# anemometer.net
KiCad netlist of a schematic drawn in EAGLE
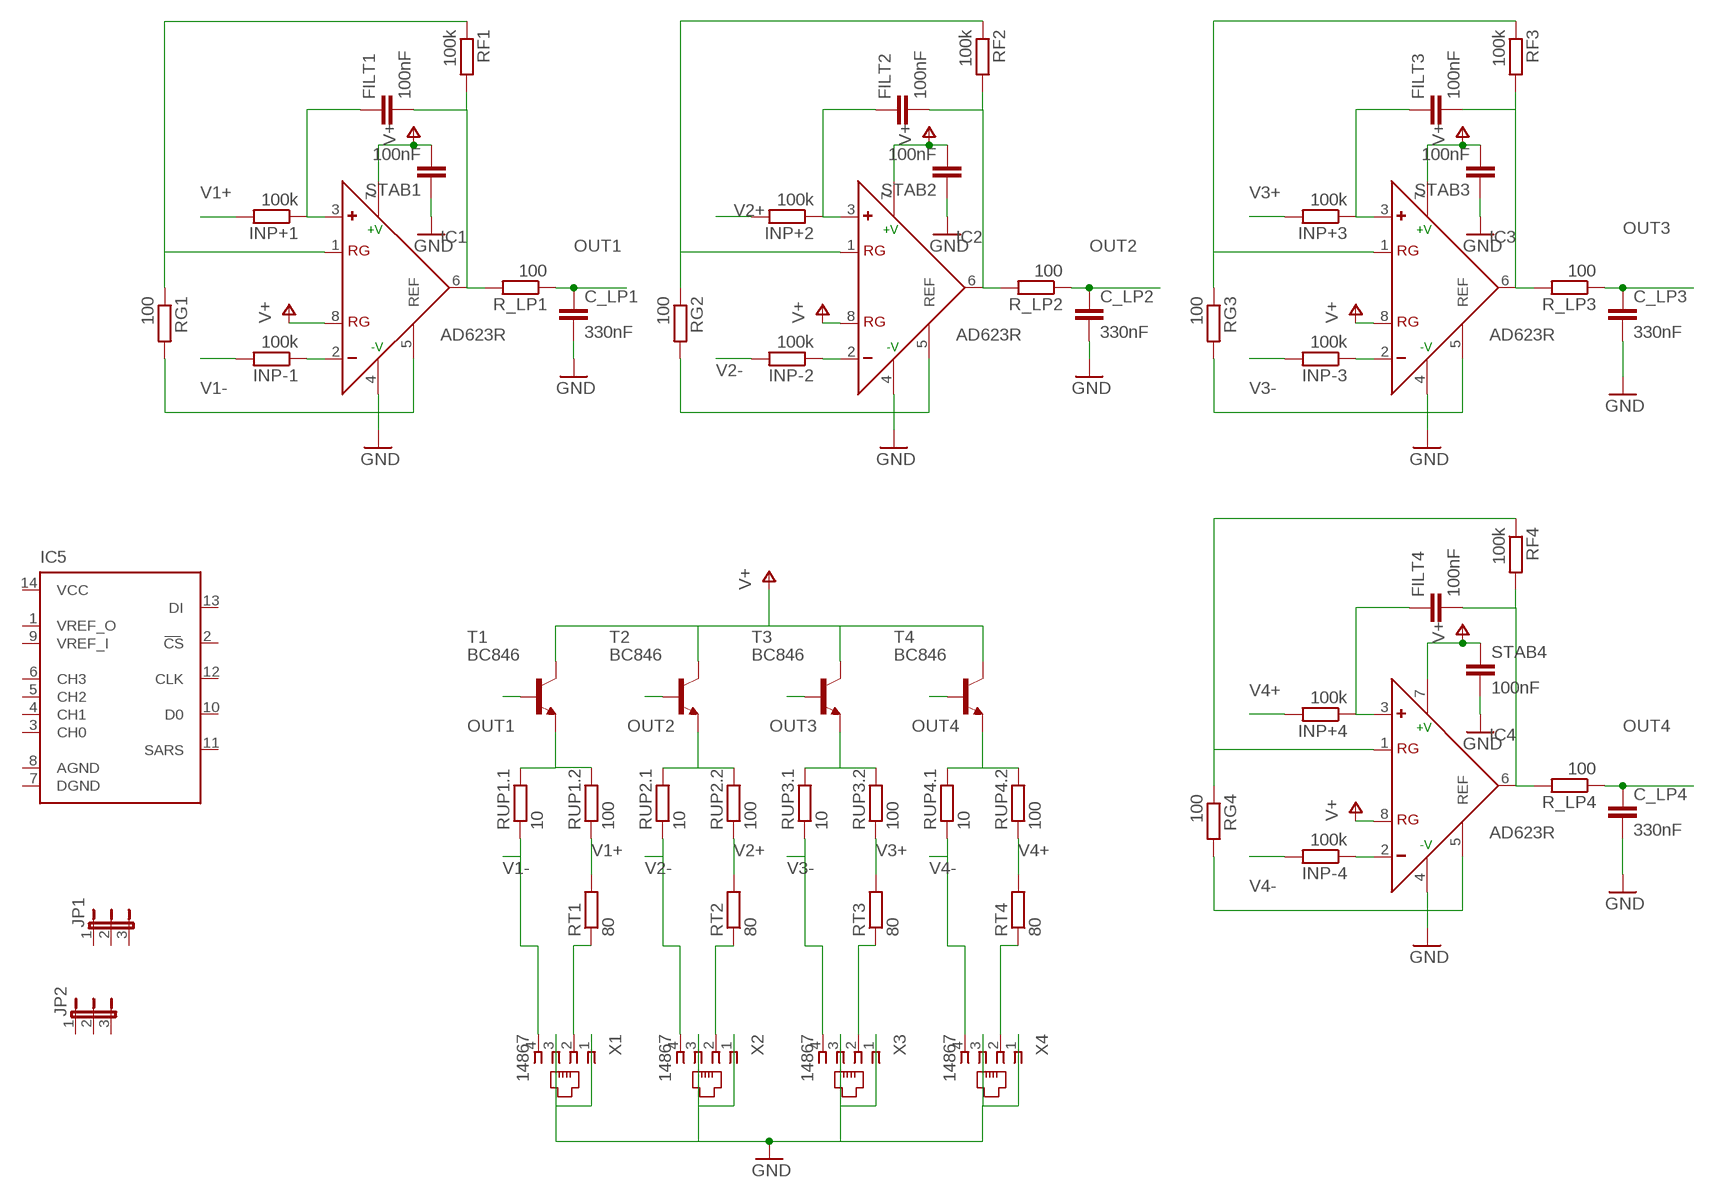
[diagram p0: schematic, sheet 1]

(export (version "E")
  (design (tool "Eeschema 10.0.6"))
  (components
    (comp (ref "C_LP1")
      (value "330nF")
      (footprint "eagle-import:C1206")
      (libsource (lib "eagle-import") (part "C-EUC1206"))
    )
    (comp (ref "C_LP2")
      (value "330nF")
      (footprint "eagle-import:C1206")
      (libsource (lib "eagle-import") (part "C-EUC1206"))
    )
    (comp (ref "C_LP3")
      (value "330nF")
      (footprint "eagle-import:C1206")
      (libsource (lib "eagle-import") (part "C-EUC1206"))
    )
    (comp (ref "C_LP4")
      (value "330nF")
      (footprint "eagle-import:C1206")
      (libsource (lib "eagle-import") (part "C-EUC1206"))
    )
    (comp (ref "FILT1")
      (value "100nF")
      (footprint "eagle-import:C1206")
      (libsource (lib "eagle-import") (part "C-EUC1206"))
    )
    (comp (ref "FILT2")
      (value "100nF")
      (footprint "eagle-import:C1206")
      (libsource (lib "eagle-import") (part "C-EUC1206"))
    )
    (comp (ref "FILT3")
      (value "100nF")
      (footprint "eagle-import:C1206")
      (libsource (lib "eagle-import") (part "C-EUC1206"))
    )
    (comp (ref "FILT4")
      (value "100nF")
      (footprint "eagle-import:C1206")
      (libsource (lib "eagle-import") (part "C-EUC1206"))
    )
    (comp (ref "IC1")
      (value "AD623R")
      (footprint "eagle-import:SO8")
      (fields (field (name "MPN") "AD623ARZ."))
      (libsource (lib "eagle-import") (part "AD623R"))
    )
    (comp (ref "IC2")
      (value "AD623R")
      (footprint "eagle-import:SO8")
      (fields (field (name "MPN") "AD623ARZ."))
      (libsource (lib "eagle-import") (part "AD623R"))
    )
    (comp (ref "IC3")
      (value "AD623R")
      (footprint "eagle-import:SO8")
      (fields (field (name "MPN") "AD623ARZ."))
      (libsource (lib "eagle-import") (part "AD623R"))
    )
    (comp (ref "IC4")
      (value "AD623R")
      (footprint "eagle-import:SO8")
      (fields (field (name "MPN") "AD623ARZ."))
      (libsource (lib "eagle-import") (part "AD623R"))
    )
    (comp (ref "IC5")
      (value "ADC08034D")
      (footprint "eagle-import:SO14")
      (libsource (lib "eagle-import") (part "ADC08034D"))
    )
    (comp (ref "INP+1")
      (value "100k")
      (footprint "eagle-import:M1206")
      (libsource (lib "eagle-import") (part "R-EU_M1206"))
    )
    (comp (ref "INP+2")
      (value "100k")
      (footprint "eagle-import:M1206")
      (libsource (lib "eagle-import") (part "R-EU_M1206"))
    )
    (comp (ref "INP+3")
      (value "100k")
      (footprint "eagle-import:M1206")
      (libsource (lib "eagle-import") (part "R-EU_M1206"))
    )
    (comp (ref "INP+4")
      (value "100k")
      (footprint "eagle-import:M1206")
      (libsource (lib "eagle-import") (part "R-EU_M1206"))
    )
    (comp (ref "INP-1")
      (value "100k")
      (footprint "eagle-import:M1206")
      (libsource (lib "eagle-import") (part "R-EU_M1206"))
    )
    (comp (ref "INP-2")
      (value "100k")
      (footprint "eagle-import:M1206")
      (libsource (lib "eagle-import") (part "R-EU_M1206"))
    )
    (comp (ref "INP-3")
      (value "100k")
      (footprint "eagle-import:M1206")
      (libsource (lib "eagle-import") (part "R-EU_M1206"))
    )
    (comp (ref "INP-4")
      (value "100k")
      (footprint "eagle-import:M1206")
      (libsource (lib "eagle-import") (part "R-EU_M1206"))
    )
    (comp (ref "JP1")
      (value "JP2E")
      (footprint "eagle-import:JP2")
      (libsource (lib "eagle-import") (part "JP2E"))
    )
    (comp (ref "JP2")
      (value "JP2E")
      (footprint "eagle-import:JP2")
      (libsource (lib "eagle-import") (part "JP2E"))
    )
    (comp (ref "RF1")
      (value "100k")
      (footprint "eagle-import:M1206")
      (libsource (lib "eagle-import") (part "R-EU_M1206"))
    )
    (comp (ref "RF2")
      (value "100k")
      (footprint "eagle-import:M1206")
      (libsource (lib "eagle-import") (part "R-EU_M1206"))
    )
    (comp (ref "RF3")
      (value "100k")
      (footprint "eagle-import:M1206")
      (libsource (lib "eagle-import") (part "R-EU_M1206"))
    )
    (comp (ref "RF4")
      (value "100k")
      (footprint "eagle-import:M1206")
      (libsource (lib "eagle-import") (part "R-EU_M1206"))
    )
    (comp (ref "RG1")
      (value "100")
      (footprint "eagle-import:M1206")
      (libsource (lib "eagle-import") (part "R-EU_M1206"))
    )
    (comp (ref "RG2")
      (value "100")
      (footprint "eagle-import:M1206")
      (libsource (lib "eagle-import") (part "R-EU_M1206"))
    )
    (comp (ref "RG3")
      (value "100")
      (footprint "eagle-import:M1206")
      (libsource (lib "eagle-import") (part "R-EU_M1206"))
    )
    (comp (ref "RG4")
      (value "100")
      (footprint "eagle-import:M1206")
      (libsource (lib "eagle-import") (part "R-EU_M1206"))
    )
    (comp (ref "RT1")
      (value "80")
      (footprint "eagle-import:R1206")
      (libsource (lib "eagle-import") (part "R-EU_R1206"))
    )
    (comp (ref "RT2")
      (value "80")
      (footprint "eagle-import:R1206")
      (libsource (lib "eagle-import") (part "R-EU_R1206"))
    )
    (comp (ref "RT3")
      (value "80")
      (footprint "eagle-import:R1206")
      (libsource (lib "eagle-import") (part "R-EU_R1206"))
    )
    (comp (ref "RT4")
      (value "80")
      (footprint "eagle-import:R1206")
      (libsource (lib "eagle-import") (part "R-EU_R1206"))
    )
    (comp (ref "RUP1.1")
      (value "10")
      (footprint "eagle-import:R1206")
      (libsource (lib "eagle-import") (part "R-EU_R1206"))
    )
    (comp (ref "RUP1.2")
      (value "100")
      (footprint "eagle-import:R1206")
      (libsource (lib "eagle-import") (part "R-EU_R1206"))
    )
    (comp (ref "RUP2.1")
      (value "10")
      (footprint "eagle-import:R1206")
      (libsource (lib "eagle-import") (part "R-EU_R1206"))
    )
    (comp (ref "RUP2.2")
      (value "100")
      (footprint "eagle-import:R1206")
      (libsource (lib "eagle-import") (part "R-EU_R1206"))
    )
    (comp (ref "RUP3.1")
      (value "10")
      (footprint "eagle-import:R1206")
      (libsource (lib "eagle-import") (part "R-EU_R1206"))
    )
    (comp (ref "RUP3.2")
      (value "100")
      (footprint "eagle-import:R1206")
      (libsource (lib "eagle-import") (part "R-EU_R1206"))
    )
    (comp (ref "RUP4.1")
      (value "10")
      (footprint "eagle-import:R1206")
      (libsource (lib "eagle-import") (part "R-EU_R1206"))
    )
    (comp (ref "RUP4.2")
      (value "100")
      (footprint "eagle-import:R1206")
      (libsource (lib "eagle-import") (part "R-EU_R1206"))
    )
    (comp (ref "R_LP1")
      (value "100")
      (footprint "eagle-import:M1206")
      (libsource (lib "eagle-import") (part "R-EU_M1206"))
    )
    (comp (ref "R_LP2")
      (value "100")
      (footprint "eagle-import:M1206")
      (libsource (lib "eagle-import") (part "R-EU_M1206"))
    )
    (comp (ref "R_LP3")
      (value "100")
      (footprint "eagle-import:M1206")
      (libsource (lib "eagle-import") (part "R-EU_M1206"))
    )
    (comp (ref "R_LP4")
      (value "100")
      (footprint "eagle-import:M1206")
      (libsource (lib "eagle-import") (part "R-EU_M1206"))
    )
    (comp (ref "STAB1")
      (value "100nF")
      (footprint "eagle-import:C1206")
      (libsource (lib "eagle-import") (part "C-EUC1206"))
    )
    (comp (ref "STAB2")
      (value "100nF")
      (footprint "eagle-import:C1206")
      (libsource (lib "eagle-import") (part "C-EUC1206"))
    )
    (comp (ref "STAB3")
      (value "100nF")
      (footprint "eagle-import:C1206")
      (libsource (lib "eagle-import") (part "C-EUC1206"))
    )
    (comp (ref "STAB4")
      (value "100nF")
      (footprint "eagle-import:C1206")
      (libsource (lib "eagle-import") (part "C-EUC1206"))
    )
    (comp (ref "T1")
      (value "BC846")
      (footprint "eagle-import:SOT23")
      (libsource (lib "eagle-import") (part "BC846"))
    )
    (comp (ref "T2")
      (value "BC846")
      (footprint "eagle-import:SOT23")
      (libsource (lib "eagle-import") (part "BC846"))
    )
    (comp (ref "T3")
      (value "BC846")
      (footprint "eagle-import:SOT23")
      (libsource (lib "eagle-import") (part "BC846"))
    )
    (comp (ref "T4")
      (value "BC846")
      (footprint "eagle-import:SOT23")
      (libsource (lib "eagle-import") (part "BC846"))
    )
    (comp (ref "X1")
      (value "14867")
      (footprint "eagle-import:14867")
      (libsource (lib "eagle-import") (part "14867"))
    )
    (comp (ref "X2")
      (value "14867")
      (footprint "eagle-import:14867")
      (libsource (lib "eagle-import") (part "14867"))
    )
    (comp (ref "X3")
      (value "14867")
      (footprint "eagle-import:14867")
      (libsource (lib "eagle-import") (part "14867"))
    )
    (comp (ref "X4")
      (value "14867")
      (footprint "eagle-import:14867")
      (libsource (lib "eagle-import") (part "14867"))
    )
  )
  (nets
    (net (code "1") (name "/AGND") (class "Default")
      (node (ref "IC5") (pin "8") (pinfunction "AGND_8") (pintype "power_in"))
    )
    (net (code "2") (name "/DGND") (class "Default")
      (node (ref "IC5") (pin "7") (pinfunction "DGND_7") (pintype "power_in"))
    )
    (net (code "3") (name "/OUT1") (class "Default")
      (node (ref "C_LP1") (pin "1") (pinfunction "1_1") (pintype "passive"))
      (node (ref "R_LP1") (pin "1") (pinfunction "1_1") (pintype "passive"))
      (node (ref "T1") (pin "1") (pinfunction "B_1") (pintype "passive"))
    )
    (net (code "4") (name "/OUT2") (class "Default")
      (node (ref "C_LP2") (pin "1") (pinfunction "1_1") (pintype "passive"))
      (node (ref "R_LP2") (pin "1") (pinfunction "1_1") (pintype "passive"))
      (node (ref "T2") (pin "1") (pinfunction "B_1") (pintype "passive"))
    )
    (net (code "5") (name "/OUT3") (class "Default")
      (node (ref "C_LP3") (pin "1") (pinfunction "1_1") (pintype "passive"))
      (node (ref "R_LP3") (pin "1") (pinfunction "1_1") (pintype "passive"))
      (node (ref "T3") (pin "1") (pinfunction "B_1") (pintype "passive"))
    )
    (net (code "6") (name "/OUT4") (class "Default")
      (node (ref "C_LP4") (pin "1") (pinfunction "1_1") (pintype "passive"))
      (node (ref "R_LP4") (pin "1") (pinfunction "1_1") (pintype "passive"))
      (node (ref "T4") (pin "1") (pinfunction "B_1") (pintype "passive"))
    )
    (net (code "7") (name "/V1+") (class "Default")
      (node (ref "INP+1") (pin "2") (pinfunction "2_2") (pintype "passive"))
      (node (ref "RT1") (pin "2") (pinfunction "2_2") (pintype "passive"))
      (node (ref "RUP1.2") (pin "1") (pinfunction "1_1") (pintype "passive"))
    )
    (net (code "8") (name "/V1-") (class "Default")
      (node (ref "INP-1") (pin "2") (pinfunction "2_2") (pintype "passive"))
      (node (ref "RUP1.1") (pin "1") (pinfunction "1_1") (pintype "passive"))
      (node (ref "X1") (pin "4") (pinfunction "4_4") (pintype "passive"))
    )
    (net (code "9") (name "/V2+") (class "Default")
      (node (ref "INP+2") (pin "2") (pinfunction "2_2") (pintype "passive"))
      (node (ref "RT2") (pin "2") (pinfunction "2_2") (pintype "passive"))
      (node (ref "RUP2.2") (pin "1") (pinfunction "1_1") (pintype "passive"))
    )
    (net (code "10") (name "/V2-") (class "Default")
      (node (ref "INP-2") (pin "2") (pinfunction "2_2") (pintype "passive"))
      (node (ref "RUP2.1") (pin "1") (pinfunction "1_1") (pintype "passive"))
      (node (ref "X2") (pin "4") (pinfunction "4_4") (pintype "passive"))
    )
    (net (code "11") (name "/V3+") (class "Default")
      (node (ref "INP+3") (pin "2") (pinfunction "2_2") (pintype "passive"))
      (node (ref "RT3") (pin "2") (pinfunction "2_2") (pintype "passive"))
      (node (ref "RUP3.2") (pin "1") (pinfunction "1_1") (pintype "passive"))
    )
    (net (code "12") (name "/V3-") (class "Default")
      (node (ref "INP-3") (pin "2") (pinfunction "2_2") (pintype "passive"))
      (node (ref "RUP3.1") (pin "1") (pinfunction "1_1") (pintype "passive"))
      (node (ref "X3") (pin "4") (pinfunction "4_4") (pintype "passive"))
    )
    (net (code "13") (name "/V4+") (class "Default")
      (node (ref "INP+4") (pin "2") (pinfunction "2_2") (pintype "passive"))
      (node (ref "RT4") (pin "2") (pinfunction "2_2") (pintype "passive"))
      (node (ref "RUP4.2") (pin "1") (pinfunction "1_1") (pintype "passive"))
    )
    (net (code "14") (name "/V4-") (class "Default")
      (node (ref "INP-4") (pin "2") (pinfunction "2_2") (pintype "passive"))
      (node (ref "RUP4.1") (pin "1") (pinfunction "1_1") (pintype "passive"))
      (node (ref "X4") (pin "4") (pinfunction "4_4") (pintype "passive"))
    )
    (net (code "15") (name "/VCC") (class "Default")
      (node (ref "IC5") (pin "14") (pinfunction "VCC_14") (pintype "power_in"))
    )
    (net (code "16") (name "GND") (class "Default")
      (node (ref "C_LP1") (pin "2") (pinfunction "2_2") (pintype "passive"))
      (node (ref "C_LP2") (pin "2") (pinfunction "2_2") (pintype "passive"))
      (node (ref "C_LP3") (pin "2") (pinfunction "2_2") (pintype "passive"))
      (node (ref "C_LP4") (pin "2") (pinfunction "2_2") (pintype "passive"))
      (node (ref "IC1") (pin "4") (pinfunction "-V_4") (pintype "power_in"))
      (node (ref "IC1") (pin "5") (pinfunction "REF_5") (pintype "passive"))
      (node (ref "IC2") (pin "4") (pinfunction "-V_4") (pintype "power_in"))
      (node (ref "IC2") (pin "5") (pinfunction "REF_5") (pintype "passive"))
      (node (ref "IC3") (pin "4") (pinfunction "-V_4") (pintype "power_in"))
      (node (ref "IC3") (pin "5") (pinfunction "REF_5") (pintype "passive"))
      (node (ref "IC4") (pin "4") (pinfunction "-V_4") (pintype "power_in"))
      (node (ref "IC4") (pin "5") (pinfunction "REF_5") (pintype "passive"))
      (node (ref "RG1") (pin "2") (pinfunction "2_2") (pintype "passive"))
      (node (ref "RG2") (pin "2") (pinfunction "2_2") (pintype "passive"))
      (node (ref "RG3") (pin "2") (pinfunction "2_2") (pintype "passive"))
      (node (ref "RG4") (pin "2") (pinfunction "2_2") (pintype "passive"))
      (node (ref "STAB1") (pin "1") (pinfunction "1_1") (pintype "passive"))
      (node (ref "STAB2") (pin "1") (pinfunction "1_1") (pintype "passive"))
      (node (ref "STAB3") (pin "1") (pinfunction "1_1") (pintype "passive"))
      (node (ref "STAB4") (pin "2") (pinfunction "2_2") (pintype "passive"))
      (node (ref "X1") (pin "1") (pinfunction "1_1") (pintype "passive"))
      (node (ref "X1") (pin "3") (pinfunction "3_3") (pintype "passive"))
      (node (ref "X2") (pin "1") (pinfunction "1_1") (pintype "passive"))
      (node (ref "X2") (pin "3") (pinfunction "3_3") (pintype "passive"))
      (node (ref "X3") (pin "1") (pinfunction "1_1") (pintype "passive"))
      (node (ref "X3") (pin "3") (pinfunction "3_3") (pintype "passive"))
      (node (ref "X4") (pin "1") (pinfunction "1_1") (pintype "passive"))
      (node (ref "X4") (pin "3") (pinfunction "3_3") (pintype "passive"))
    )
    (net (code "17") (name "Net-(IC1-+)") (class "Default")
      (node (ref "FILT1") (pin "1") (pinfunction "1_1") (pintype "passive"))
      (node (ref "IC1") (pin "3") (pinfunction "+_3") (pintype "input"))
      (node (ref "INP+1") (pin "1") (pinfunction "1_1") (pintype "passive"))
    )
    (net (code "18") (name "Net-(IC1--)") (class "Default")
      (node (ref "IC1") (pin "2") (pinfunction "-_2") (pintype "input"))
      (node (ref "INP-1") (pin "1") (pinfunction "1_1") (pintype "passive"))
    )
    (net (code "19") (name "Net-(IC1-OUT)") (class "Default")
      (node (ref "FILT1") (pin "2") (pinfunction "2_2") (pintype "passive"))
      (node (ref "IC1") (pin "6") (pinfunction "OUT_6") (pintype "output"))
      (node (ref "RF1") (pin "2") (pinfunction "2_2") (pintype "passive"))
      (node (ref "R_LP1") (pin "2") (pinfunction "2_2") (pintype "passive"))
    )
    (net (code "20") (name "Net-(IC1-RG-Pad1)") (class "Default")
      (node (ref "IC1") (pin "1") (pinfunction "RG_1") (pintype "passive"))
      (node (ref "RF1") (pin "1") (pinfunction "1_1") (pintype "passive"))
      (node (ref "RG1") (pin "1") (pinfunction "1_1") (pintype "passive"))
    )
    (net (code "21") (name "Net-(IC2-+)") (class "Default")
      (node (ref "FILT2") (pin "1") (pinfunction "1_1") (pintype "passive"))
      (node (ref "IC2") (pin "3") (pinfunction "+_3") (pintype "input"))
      (node (ref "INP+2") (pin "1") (pinfunction "1_1") (pintype "passive"))
    )
    (net (code "22") (name "Net-(IC2--)") (class "Default")
      (node (ref "IC2") (pin "2") (pinfunction "-_2") (pintype "input"))
      (node (ref "INP-2") (pin "1") (pinfunction "1_1") (pintype "passive"))
    )
    (net (code "23") (name "Net-(IC2-OUT)") (class "Default")
      (node (ref "FILT2") (pin "2") (pinfunction "2_2") (pintype "passive"))
      (node (ref "IC2") (pin "6") (pinfunction "OUT_6") (pintype "output"))
      (node (ref "RF2") (pin "2") (pinfunction "2_2") (pintype "passive"))
      (node (ref "R_LP2") (pin "2") (pinfunction "2_2") (pintype "passive"))
    )
    (net (code "24") (name "Net-(IC2-RG-Pad1)") (class "Default")
      (node (ref "IC2") (pin "1") (pinfunction "RG_1") (pintype "passive"))
      (node (ref "RF2") (pin "1") (pinfunction "1_1") (pintype "passive"))
      (node (ref "RG2") (pin "1") (pinfunction "1_1") (pintype "passive"))
    )
    (net (code "25") (name "Net-(IC3-+)") (class "Default")
      (node (ref "FILT3") (pin "1") (pinfunction "1_1") (pintype "passive"))
      (node (ref "IC3") (pin "3") (pinfunction "+_3") (pintype "input"))
      (node (ref "INP+3") (pin "1") (pinfunction "1_1") (pintype "passive"))
    )
    (net (code "26") (name "Net-(IC3--)") (class "Default")
      (node (ref "IC3") (pin "2") (pinfunction "-_2") (pintype "input"))
      (node (ref "INP-3") (pin "1") (pinfunction "1_1") (pintype "passive"))
    )
    (net (code "27") (name "Net-(IC3-OUT)") (class "Default")
      (node (ref "FILT3") (pin "2") (pinfunction "2_2") (pintype "passive"))
      (node (ref "IC3") (pin "6") (pinfunction "OUT_6") (pintype "output"))
      (node (ref "RF3") (pin "2") (pinfunction "2_2") (pintype "passive"))
      (node (ref "R_LP3") (pin "2") (pinfunction "2_2") (pintype "passive"))
    )
    (net (code "28") (name "Net-(IC3-RG-Pad1)") (class "Default")
      (node (ref "IC3") (pin "1") (pinfunction "RG_1") (pintype "passive"))
      (node (ref "RF3") (pin "1") (pinfunction "1_1") (pintype "passive"))
      (node (ref "RG3") (pin "1") (pinfunction "1_1") (pintype "passive"))
    )
    (net (code "29") (name "Net-(IC4-+)") (class "Default")
      (node (ref "FILT4") (pin "1") (pinfunction "1_1") (pintype "passive"))
      (node (ref "IC4") (pin "3") (pinfunction "+_3") (pintype "input"))
      (node (ref "INP+4") (pin "1") (pinfunction "1_1") (pintype "passive"))
    )
    (net (code "30") (name "Net-(IC4--)") (class "Default")
      (node (ref "IC4") (pin "2") (pinfunction "-_2") (pintype "input"))
      (node (ref "INP-4") (pin "1") (pinfunction "1_1") (pintype "passive"))
    )
    (net (code "31") (name "Net-(IC4-OUT)") (class "Default")
      (node (ref "FILT4") (pin "2") (pinfunction "2_2") (pintype "passive"))
      (node (ref "IC4") (pin "6") (pinfunction "OUT_6") (pintype "output"))
      (node (ref "RF4") (pin "2") (pinfunction "2_2") (pintype "passive"))
      (node (ref "R_LP4") (pin "2") (pinfunction "2_2") (pintype "passive"))
    )
    (net (code "32") (name "Net-(IC4-RG-Pad1)") (class "Default")
      (node (ref "IC4") (pin "1") (pinfunction "RG_1") (pintype "passive"))
      (node (ref "RF4") (pin "1") (pinfunction "1_1") (pintype "passive"))
      (node (ref "RG4") (pin "1") (pinfunction "1_1") (pintype "passive"))
    )
    (net (code "33") (name "Net-(RT1-Pad1)") (class "Default")
      (node (ref "RT1") (pin "1") (pinfunction "1_1") (pintype "passive"))
      (node (ref "X1") (pin "2") (pinfunction "2_2") (pintype "passive"))
    )
    (net (code "34") (name "Net-(RT2-Pad1)") (class "Default")
      (node (ref "RT2") (pin "1") (pinfunction "1_1") (pintype "passive"))
      (node (ref "X2") (pin "2") (pinfunction "2_2") (pintype "passive"))
    )
    (net (code "35") (name "Net-(RT3-Pad1)") (class "Default")
      (node (ref "RT3") (pin "1") (pinfunction "1_1") (pintype "passive"))
      (node (ref "X3") (pin "2") (pinfunction "2_2") (pintype "passive"))
    )
    (net (code "36") (name "Net-(RT4-Pad1)") (class "Default")
      (node (ref "RT4") (pin "1") (pinfunction "1_1") (pintype "passive"))
      (node (ref "X4") (pin "2") (pinfunction "2_2") (pintype "passive"))
    )
    (net (code "37") (name "Net-(T1-E)") (class "Default")
      (node (ref "RUP1.1") (pin "2") (pinfunction "2_2") (pintype "passive"))
      (node (ref "RUP1.2") (pin "2") (pinfunction "2_2") (pintype "passive"))
      (node (ref "T1") (pin "2") (pinfunction "E_2") (pintype "passive"))
    )
    (net (code "38") (name "Net-(T2-E)") (class "Default")
      (node (ref "RUP2.1") (pin "2") (pinfunction "2_2") (pintype "passive"))
      (node (ref "RUP2.2") (pin "2") (pinfunction "2_2") (pintype "passive"))
      (node (ref "T2") (pin "2") (pinfunction "E_2") (pintype "passive"))
    )
    (net (code "39") (name "Net-(T3-E)") (class "Default")
      (node (ref "RUP3.1") (pin "2") (pinfunction "2_2") (pintype "passive"))
      (node (ref "RUP3.2") (pin "2") (pinfunction "2_2") (pintype "passive"))
      (node (ref "T3") (pin "2") (pinfunction "E_2") (pintype "passive"))
    )
    (net (code "40") (name "Net-(T4-E)") (class "Default")
      (node (ref "RUP4.1") (pin "2") (pinfunction "2_2") (pintype "passive"))
      (node (ref "RUP4.2") (pin "2") (pinfunction "2_2") (pintype "passive"))
      (node (ref "T4") (pin "2") (pinfunction "E_2") (pintype "passive"))
    )
    (net (code "41") (name "V+") (class "Default")
      (node (ref "IC1") (pin "7") (pinfunction "+V_7") (pintype "power_in"))
      (node (ref "IC1") (pin "8") (pinfunction "RG_8") (pintype "passive"))
      (node (ref "IC2") (pin "7") (pinfunction "+V_7") (pintype "power_in"))
      (node (ref "IC2") (pin "8") (pinfunction "RG_8") (pintype "passive"))
      (node (ref "IC3") (pin "7") (pinfunction "+V_7") (pintype "power_in"))
      (node (ref "IC3") (pin "8") (pinfunction "RG_8") (pintype "passive"))
      (node (ref "IC4") (pin "7") (pinfunction "+V_7") (pintype "power_in"))
      (node (ref "IC4") (pin "8") (pinfunction "RG_8") (pintype "passive"))
      (node (ref "STAB1") (pin "2") (pinfunction "2_2") (pintype "passive"))
      (node (ref "STAB2") (pin "2") (pinfunction "2_2") (pintype "passive"))
      (node (ref "STAB3") (pin "2") (pinfunction "2_2") (pintype "passive"))
      (node (ref "STAB4") (pin "1") (pinfunction "1_1") (pintype "passive"))
      (node (ref "T1") (pin "3") (pinfunction "C_3") (pintype "passive"))
      (node (ref "T2") (pin "3") (pinfunction "C_3") (pintype "passive"))
      (node (ref "T3") (pin "3") (pinfunction "C_3") (pintype "passive"))
      (node (ref "T4") (pin "3") (pinfunction "C_3") (pintype "passive"))
    )
    (net (code "42") (name "unconnected-(IC5-CH0-Pad3)") (class "Default")
      (node (ref "IC5") (pin "3") (pinfunction "CH0_3") (pintype "input"))
    )
    (net (code "43") (name "unconnected-(IC5-CH1-Pad4)") (class "Default")
      (node (ref "IC5") (pin "4") (pinfunction "CH1_4") (pintype "input"))
    )
    (net (code "44") (name "unconnected-(IC5-CH2-Pad5)") (class "Default")
      (node (ref "IC5") (pin "5") (pinfunction "CH2_5") (pintype "input"))
    )
    (net (code "45") (name "unconnected-(IC5-CH3-Pad6)") (class "Default")
      (node (ref "IC5") (pin "6") (pinfunction "CH3_6") (pintype "input"))
    )
    (net (code "46") (name "unconnected-(IC5-CLK-Pad12)") (class "Default")
      (node (ref "IC5") (pin "12") (pinfunction "CLK_12") (pintype "input"))
    )
    (net (code "47") (name "unconnected-(IC5-CS-Pad2)") (class "Default")
      (node (ref "IC5") (pin "2") (pinfunction "CS_2") (pintype "input"))
    )
    (net (code "48") (name "unconnected-(IC5-D0-Pad10)") (class "Default")
      (node (ref "IC5") (pin "10") (pinfunction "D0_10") (pintype "tri_state"))
    )
    (net (code "49") (name "unconnected-(IC5-DI-Pad13)") (class "Default")
      (node (ref "IC5") (pin "13") (pinfunction "DI_13") (pintype "input"))
    )
    (net (code "50") (name "unconnected-(IC5-SARS-Pad11)") (class "Default")
      (node (ref "IC5") (pin "11") (pinfunction "SARS_11") (pintype "output"))
    )
    (net (code "51") (name "unconnected-(IC5-VREF_I-Pad9)") (class "Default")
      (node (ref "IC5") (pin "9") (pinfunction "VREF_I_9") (pintype "input"))
    )
    (net (code "52") (name "unconnected-(IC5-VREF_O-Pad1)") (class "Default")
      (node (ref "IC5") (pin "1") (pinfunction "VREF_O_1") (pintype "output"))
    )
    (net (code "53") (name "unconnected-(JP1-Pad1)") (class "Default")
      (node (ref "JP1") (pin "1") (pinfunction "1_1") (pintype "passive"))
    )
    (net (code "54") (name "unconnected-(JP1-Pad2)") (class "Default")
      (node (ref "JP1") (pin "2") (pinfunction "2_2") (pintype "passive"))
    )
    (net (code "55") (name "unconnected-(JP1-Pad3)") (class "Default")
      (node (ref "JP1") (pin "3") (pinfunction "3_3") (pintype "passive"))
    )
    (net (code "56") (name "unconnected-(JP2-Pad1)") (class "Default")
      (node (ref "JP2") (pin "1") (pinfunction "1_1") (pintype "passive"))
    )
    (net (code "57") (name "unconnected-(JP2-Pad2)") (class "Default")
      (node (ref "JP2") (pin "2") (pinfunction "2_2") (pintype "passive"))
    )
    (net (code "58") (name "unconnected-(JP2-Pad3)") (class "Default")
      (node (ref "JP2") (pin "3") (pinfunction "3_3") (pintype "passive"))
    )
  )
)
